# FPGA_PWR_CONFIG.net
KiCad netlist of a schematic drawn in Altium Designer
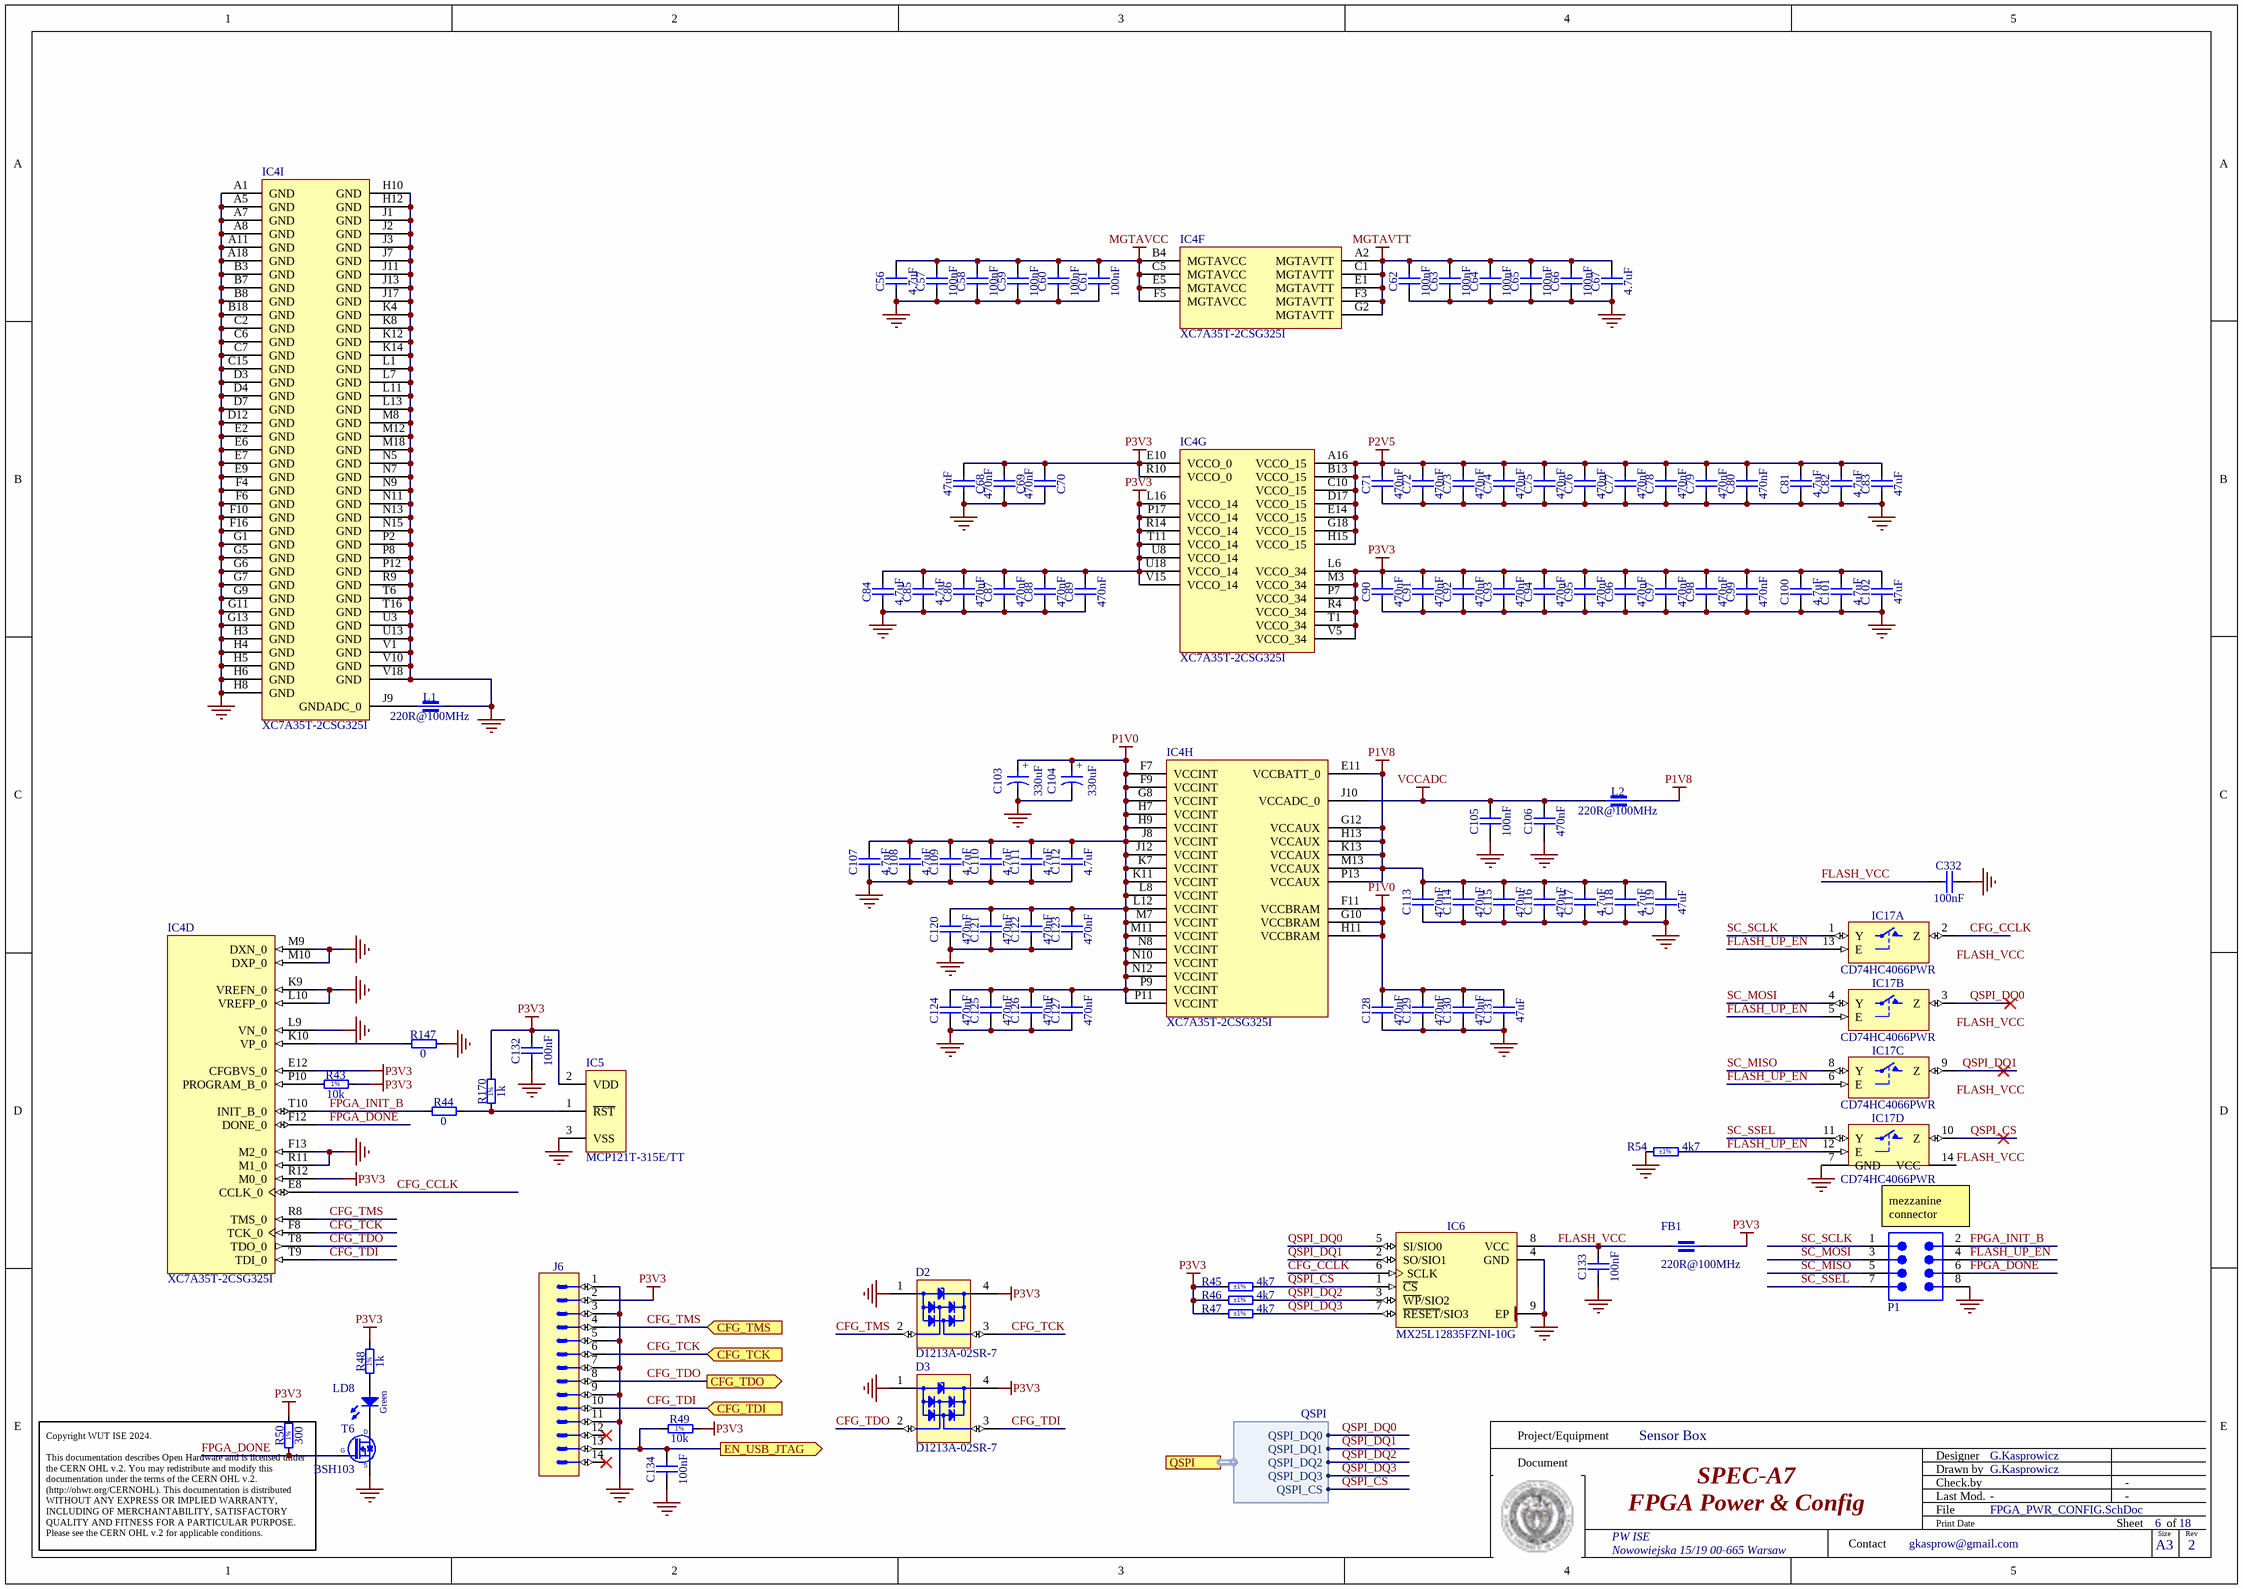
[diagram p0: FPGA_PWR_CONFIG.SchDoc]

(export (version "E")
  (design (tool "Eeschema 10.0.6"))
  (components
    (comp (ref "C56")
      (value "4.7uF")
      (footprint "CAPC1005X55N")
      (description "Non-polarised capacitor")
      (fields
        (field (name "PART NUMBER") "CC0402_4.7UF_6.3V_20%_X5R")
        (field (name "VOLTAGE") "6.3V")
        (field (name "AUTHOR") "CERN DEM JLC")
      )
      (libsource (lib "Capacitors") (part "Capacitor - non polarized"))
    )
    (comp (ref "C57")
      (value "100nF")
      (footprint "CAPC0603X33N")
      (description "Non-polarised capacitor")
      (fields
        (field (name "PART NUMBER") "CC0201_100NF_6.3V_10%_X5R")
        (field (name "VOLTAGE") "6.3V")
        (field (name "AUTHOR") "CERN DEM JLC")
      )
      (libsource (lib "Capacitors") (part "Capacitor - non polarized"))
    )
    (comp (ref "C58")
      (value "100nF")
      (footprint "CAPC0603X33N")
      (description "Non-polarised capacitor")
      (fields
        (field (name "PART NUMBER") "CC0201_100NF_6.3V_10%_X5R")
        (field (name "VOLTAGE") "6.3V")
        (field (name "AUTHOR") "CERN DEM JLC")
      )
      (libsource (lib "Capacitors") (part "Capacitor - non polarized"))
    )
    (comp (ref "C59")
      (value "100nF")
      (footprint "CAPC0603X33N")
      (description "Non-polarised capacitor")
      (fields
        (field (name "PART NUMBER") "CC0201_100NF_6.3V_10%_X5R")
        (field (name "VOLTAGE") "6.3V")
        (field (name "AUTHOR") "CERN DEM JLC")
      )
      (libsource (lib "Capacitors") (part "Capacitor - non polarized"))
    )
    (comp (ref "C60")
      (value "100nF")
      (footprint "CAPC0603X33N")
      (description "Non-polarised capacitor")
      (fields
        (field (name "PART NUMBER") "CC0201_100NF_6.3V_10%_X5R")
        (field (name "VOLTAGE") "6.3V")
        (field (name "AUTHOR") "CERN DEM JLC")
      )
      (libsource (lib "Capacitors") (part "Capacitor - non polarized"))
    )
    (comp (ref "C61")
      (value "100nF")
      (footprint "CAPC0603X33N")
      (description "Non-polarised capacitor")
      (fields
        (field (name "PART NUMBER") "CC0201_100NF_6.3V_10%_X5R")
        (field (name "VOLTAGE") "6.3V")
        (field (name "AUTHOR") "CERN DEM JLC")
      )
      (libsource (lib "Capacitors") (part "Capacitor - non polarized"))
    )
    (comp (ref "C62")
      (value "100nF")
      (footprint "CAPC0603X33N")
      (description "Non-polarised capacitor")
      (fields
        (field (name "PART NUMBER") "CC0201_100NF_6.3V_10%_X5R")
        (field (name "VOLTAGE") "6.3V")
        (field (name "AUTHOR") "CERN DEM JLC")
      )
      (libsource (lib "Capacitors") (part "Capacitor - non polarized"))
    )
    (comp (ref "C63")
      (value "100nF")
      (footprint "CAPC0603X33N")
      (description "Non-polarised capacitor")
      (fields
        (field (name "PART NUMBER") "CC0201_100NF_6.3V_10%_X5R")
        (field (name "VOLTAGE") "6.3V")
        (field (name "AUTHOR") "CERN DEM JLC")
      )
      (libsource (lib "Capacitors") (part "Capacitor - non polarized"))
    )
    (comp (ref "C64")
      (value "100nF")
      (footprint "CAPC0603X33N")
      (description "Non-polarised capacitor")
      (fields
        (field (name "PART NUMBER") "CC0201_100NF_6.3V_10%_X5R")
        (field (name "VOLTAGE") "6.3V")
        (field (name "AUTHOR") "CERN DEM JLC")
      )
      (libsource (lib "Capacitors") (part "Capacitor - non polarized"))
    )
    (comp (ref "C65")
      (value "100nF")
      (footprint "CAPC0603X33N")
      (description "Non-polarised capacitor")
      (fields
        (field (name "PART NUMBER") "CC0201_100NF_6.3V_10%_X5R")
        (field (name "VOLTAGE") "6.3V")
        (field (name "AUTHOR") "CERN DEM JLC")
      )
      (libsource (lib "Capacitors") (part "Capacitor - non polarized"))
    )
    (comp (ref "C66")
      (value "100nF")
      (footprint "CAPC0603X33N")
      (description "Non-polarised capacitor")
      (fields
        (field (name "PART NUMBER") "CC0201_100NF_6.3V_10%_X5R")
        (field (name "VOLTAGE") "6.3V")
        (field (name "AUTHOR") "CERN DEM JLC")
      )
      (libsource (lib "Capacitors") (part "Capacitor - non polarized"))
    )
    (comp (ref "C67")
      (value "4.7uF")
      (footprint "CAPC1005X55N")
      (description "Non-polarised capacitor")
      (fields
        (field (name "PART NUMBER") "CC0402_4.7UF_6.3V_20%_X5R")
        (field (name "VOLTAGE") "6.3V")
        (field (name "AUTHOR") "CERN DEM JLC")
      )
      (libsource (lib "Capacitors") (part "Capacitor - non polarized"))
    )
    (comp (ref "C68")
      (value "47uF")
      (footprint "CAPC1608X100N")
      (description "Non-polarised capacitor")
      (fields
        (field (name "PART NUMBER") "CC0603_47UF_6.3V_20%_X5R")
        (field (name "VOLTAGE") "6.3V")
        (field (name "AUTHOR") "CERN DEM JLC")
      )
      (libsource (lib "Capacitors") (part "Capacitor - non polarized"))
    )
    (comp (ref "C69")
      (value "470nF")
      (footprint "CAPC0603X33N")
      (description "Non-polarised capacitor")
      (fields
        (field (name "PART NUMBER") "CC0201_470NF_4V_20%_X5R")
        (field (name "VOLTAGE") "4V")
        (field (name "AUTHOR") "CERN DEM JLC")
      )
      (libsource (lib "Capacitors") (part "Capacitor - non polarized"))
    )
    (comp (ref "C70")
      (value "470nF")
      (footprint "CAPC0603X33N")
      (description "Non-polarised capacitor")
      (fields
        (field (name "PART NUMBER") "CC0201_470NF_4V_20%_X5R")
        (field (name "VOLTAGE") "4V")
        (field (name "AUTHOR") "CERN DEM JLC")
      )
      (libsource (lib "Capacitors") (part "Capacitor - non polarized"))
    )
    (comp (ref "C71")
      (value "470nF")
      (footprint "CAPC0603X33N")
      (description "Non-polarised capacitor")
      (fields
        (field (name "PART NUMBER") "CC0201_470NF_4V_20%_X5R")
        (field (name "VOLTAGE") "4V")
        (field (name "AUTHOR") "CERN DEM JLC")
      )
      (libsource (lib "Capacitors") (part "Capacitor - non polarized"))
    )
    (comp (ref "C72")
      (value "470nF")
      (footprint "CAPC0603X33N")
      (description "Non-polarised capacitor")
      (fields
        (field (name "PART NUMBER") "CC0201_470NF_4V_20%_X5R")
        (field (name "VOLTAGE") "4V")
        (field (name "AUTHOR") "CERN DEM JLC")
      )
      (libsource (lib "Capacitors") (part "Capacitor - non polarized"))
    )
    (comp (ref "C73")
      (value "470nF")
      (footprint "CAPC0603X33N")
      (description "Non-polarised capacitor")
      (fields
        (field (name "PART NUMBER") "CC0201_470NF_4V_20%_X5R")
        (field (name "VOLTAGE") "4V")
        (field (name "AUTHOR") "CERN DEM JLC")
      )
      (libsource (lib "Capacitors") (part "Capacitor - non polarized"))
    )
    (comp (ref "C74")
      (value "470nF")
      (footprint "CAPC0603X33N")
      (description "Non-polarised capacitor")
      (fields
        (field (name "PART NUMBER") "CC0201_470NF_4V_20%_X5R")
        (field (name "VOLTAGE") "4V")
        (field (name "AUTHOR") "CERN DEM JLC")
      )
      (libsource (lib "Capacitors") (part "Capacitor - non polarized"))
    )
    (comp (ref "C75")
      (value "470nF")
      (footprint "CAPC0603X33N")
      (description "Non-polarised capacitor")
      (fields
        (field (name "PART NUMBER") "CC0201_470NF_4V_20%_X5R")
        (field (name "VOLTAGE") "4V")
        (field (name "AUTHOR") "CERN DEM JLC")
      )
      (libsource (lib "Capacitors") (part "Capacitor - non polarized"))
    )
    (comp (ref "C76")
      (value "470nF")
      (footprint "CAPC0603X33N")
      (description "Non-polarised capacitor")
      (fields
        (field (name "PART NUMBER") "CC0201_470NF_4V_20%_X5R")
        (field (name "VOLTAGE") "4V")
        (field (name "AUTHOR") "CERN DEM JLC")
      )
      (libsource (lib "Capacitors") (part "Capacitor - non polarized"))
    )
    (comp (ref "C77")
      (value "470nF")
      (footprint "CAPC0603X33N")
      (description "Non-polarised capacitor")
      (fields
        (field (name "PART NUMBER") "CC0201_470NF_4V_20%_X5R")
        (field (name "VOLTAGE") "4V")
        (field (name "AUTHOR") "CERN DEM JLC")
      )
      (libsource (lib "Capacitors") (part "Capacitor - non polarized"))
    )
    (comp (ref "C78")
      (value "470nF")
      (footprint "CAPC0603X33N")
      (description "Non-polarised capacitor")
      (fields
        (field (name "PART NUMBER") "CC0201_470NF_4V_20%_X5R")
        (field (name "VOLTAGE") "4V")
        (field (name "AUTHOR") "CERN DEM JLC")
      )
      (libsource (lib "Capacitors") (part "Capacitor - non polarized"))
    )
    (comp (ref "C79")
      (value "470nF")
      (footprint "CAPC0603X33N")
      (description "Non-polarised capacitor")
      (fields
        (field (name "PART NUMBER") "CC0201_470NF_4V_20%_X5R")
        (field (name "VOLTAGE") "4V")
        (field (name "AUTHOR") "CERN DEM JLC")
      )
      (libsource (lib "Capacitors") (part "Capacitor - non polarized"))
    )
    (comp (ref "C80")
      (value "470nF")
      (footprint "CAPC0603X33N")
      (description "Non-polarised capacitor")
      (fields
        (field (name "PART NUMBER") "CC0201_470NF_4V_20%_X5R")
        (field (name "VOLTAGE") "4V")
        (field (name "AUTHOR") "CERN DEM JLC")
      )
      (libsource (lib "Capacitors") (part "Capacitor - non polarized"))
    )
    (comp (ref "C81")
      (value "4.7uF")
      (footprint "CAPC1005X55N")
      (description "Non-polarised capacitor")
      (fields
        (field (name "PART NUMBER") "CC0402_4.7UF_6.3V_20%_X5R")
        (field (name "VOLTAGE") "6.3V")
        (field (name "AUTHOR") "CERN DEM JLC")
      )
      (libsource (lib "Capacitors") (part "Capacitor - non polarized"))
    )
    (comp (ref "C82")
      (value "4.7uF")
      (footprint "CAPC1005X55N")
      (description "Non-polarised capacitor")
      (fields
        (field (name "PART NUMBER") "CC0402_4.7UF_6.3V_20%_X5R")
        (field (name "VOLTAGE") "6.3V")
        (field (name "AUTHOR") "CERN DEM JLC")
      )
      (libsource (lib "Capacitors") (part "Capacitor - non polarized"))
    )
    (comp (ref "C83")
      (value "47uF")
      (footprint "CAPC1608X100N")
      (description "Non-polarised capacitor")
      (fields
        (field (name "PART NUMBER") "CC0603_47UF_6.3V_20%_X5R")
        (field (name "VOLTAGE") "6.3V")
        (field (name "AUTHOR") "CERN DEM JLC")
      )
      (libsource (lib "Capacitors") (part "Capacitor - non polarized"))
    )
    (comp (ref "C84")
      (value "4.7uF")
      (footprint "CAPC1005X55N")
      (description "Non-polarised capacitor")
      (fields
        (field (name "PART NUMBER") "CC0402_4.7UF_6.3V_20%_X5R")
        (field (name "VOLTAGE") "6.3V")
        (field (name "AUTHOR") "CERN DEM JLC")
      )
      (libsource (lib "Capacitors") (part "Capacitor - non polarized"))
    )
    (comp (ref "C85")
      (value "4.7uF")
      (footprint "CAPC1005X55N")
      (description "Non-polarised capacitor")
      (fields
        (field (name "PART NUMBER") "CC0402_4.7UF_6.3V_20%_X5R")
        (field (name "VOLTAGE") "6.3V")
        (field (name "AUTHOR") "CERN DEM JLC")
      )
      (libsource (lib "Capacitors") (part "Capacitor - non polarized"))
    )
    (comp (ref "C86")
      (value "470nF")
      (footprint "CAPC0603X33N")
      (description "Non-polarised capacitor")
      (fields
        (field (name "PART NUMBER") "CC0201_470NF_4V_20%_X5R")
        (field (name "VOLTAGE") "4V")
        (field (name "AUTHOR") "CERN DEM JLC")
      )
      (libsource (lib "Capacitors") (part "Capacitor - non polarized"))
    )
    (comp (ref "C87")
      (value "470nF")
      (footprint "CAPC0603X33N")
      (description "Non-polarised capacitor")
      (fields
        (field (name "PART NUMBER") "CC0201_470NF_4V_20%_X5R")
        (field (name "VOLTAGE") "4V")
        (field (name "AUTHOR") "CERN DEM JLC")
      )
      (libsource (lib "Capacitors") (part "Capacitor - non polarized"))
    )
    (comp (ref "C88")
      (value "470nF")
      (footprint "CAPC0603X33N")
      (description "Non-polarised capacitor")
      (fields
        (field (name "PART NUMBER") "CC0201_470NF_4V_20%_X5R")
        (field (name "VOLTAGE") "4V")
        (field (name "AUTHOR") "CERN DEM JLC")
      )
      (libsource (lib "Capacitors") (part "Capacitor - non polarized"))
    )
    (comp (ref "C89")
      (value "470nF")
      (footprint "CAPC0603X33N")
      (description "Non-polarised capacitor")
      (fields
        (field (name "PART NUMBER") "CC0201_470NF_4V_20%_X5R")
        (field (name "VOLTAGE") "4V")
        (field (name "AUTHOR") "CERN DEM JLC")
      )
      (libsource (lib "Capacitors") (part "Capacitor - non polarized"))
    )
    (comp (ref "C90")
      (value "470nF")
      (footprint "CAPC0603X33N")
      (description "Non-polarised capacitor")
      (fields
        (field (name "PART NUMBER") "CC0201_470NF_4V_20%_X5R")
        (field (name "VOLTAGE") "4V")
        (field (name "AUTHOR") "CERN DEM JLC")
      )
      (libsource (lib "Capacitors") (part "Capacitor - non polarized"))
    )
    (comp (ref "C91")
      (value "470nF")
      (footprint "CAPC0603X33N")
      (description "Non-polarised capacitor")
      (fields
        (field (name "PART NUMBER") "CC0201_470NF_4V_20%_X5R")
        (field (name "VOLTAGE") "4V")
        (field (name "AUTHOR") "CERN DEM JLC")
      )
      (libsource (lib "Capacitors") (part "Capacitor - non polarized"))
    )
    (comp (ref "C92")
      (value "470nF")
      (footprint "CAPC0603X33N")
      (description "Non-polarised capacitor")
      (fields
        (field (name "PART NUMBER") "CC0201_470NF_4V_20%_X5R")
        (field (name "VOLTAGE") "4V")
        (field (name "AUTHOR") "CERN DEM JLC")
      )
      (libsource (lib "Capacitors") (part "Capacitor - non polarized"))
    )
    (comp (ref "C93")
      (value "470nF")
      (footprint "CAPC0603X33N")
      (description "Non-polarised capacitor")
      (fields
        (field (name "PART NUMBER") "CC0201_470NF_4V_20%_X5R")
        (field (name "VOLTAGE") "4V")
        (field (name "AUTHOR") "CERN DEM JLC")
      )
      (libsource (lib "Capacitors") (part "Capacitor - non polarized"))
    )
    (comp (ref "C94")
      (value "470nF")
      (footprint "CAPC0603X33N")
      (description "Non-polarised capacitor")
      (fields
        (field (name "PART NUMBER") "CC0201_470NF_4V_20%_X5R")
        (field (name "VOLTAGE") "4V")
        (field (name "AUTHOR") "CERN DEM JLC")
      )
      (libsource (lib "Capacitors") (part "Capacitor - non polarized"))
    )
    (comp (ref "C95")
      (value "470nF")
      (footprint "CAPC0603X33N")
      (description "Non-polarised capacitor")
      (fields
        (field (name "PART NUMBER") "CC0201_470NF_4V_20%_X5R")
        (field (name "VOLTAGE") "4V")
        (field (name "AUTHOR") "CERN DEM JLC")
      )
      (libsource (lib "Capacitors") (part "Capacitor - non polarized"))
    )
    (comp (ref "C96")
      (value "470nF")
      (footprint "CAPC0603X33N")
      (description "Non-polarised capacitor")
      (fields
        (field (name "PART NUMBER") "CC0201_470NF_4V_20%_X5R")
        (field (name "VOLTAGE") "4V")
        (field (name "AUTHOR") "CERN DEM JLC")
      )
      (libsource (lib "Capacitors") (part "Capacitor - non polarized"))
    )
    (comp (ref "C97")
      (value "470nF")
      (footprint "CAPC0603X33N")
      (description "Non-polarised capacitor")
      (fields
        (field (name "PART NUMBER") "CC0201_470NF_4V_20%_X5R")
        (field (name "VOLTAGE") "4V")
        (field (name "AUTHOR") "CERN DEM JLC")
      )
      (libsource (lib "Capacitors") (part "Capacitor - non polarized"))
    )
    (comp (ref "C98")
      (value "470nF")
      (footprint "CAPC0603X33N")
      (description "Non-polarised capacitor")
      (fields
        (field (name "PART NUMBER") "CC0201_470NF_4V_20%_X5R")
        (field (name "VOLTAGE") "4V")
        (field (name "AUTHOR") "CERN DEM JLC")
      )
      (libsource (lib "Capacitors") (part "Capacitor - non polarized"))
    )
    (comp (ref "C99")
      (value "470nF")
      (footprint "CAPC0603X33N")
      (description "Non-polarised capacitor")
      (fields
        (field (name "PART NUMBER") "CC0201_470NF_4V_20%_X5R")
        (field (name "VOLTAGE") "4V")
        (field (name "AUTHOR") "CERN DEM JLC")
      )
      (libsource (lib "Capacitors") (part "Capacitor - non polarized"))
    )
    (comp (ref "C100")
      (value "4.7uF")
      (footprint "CAPC1005X55N")
      (description "Non-polarised capacitor")
      (fields
        (field (name "PART NUMBER") "CC0402_4.7UF_6.3V_20%_X5R")
        (field (name "VOLTAGE") "6.3V")
        (field (name "AUTHOR") "CERN DEM JLC")
      )
      (libsource (lib "Capacitors") (part "Capacitor - non polarized"))
    )
    (comp (ref "C101")
      (value "4.7uF")
      (footprint "CAPC1005X55N")
      (description "Non-polarised capacitor")
      (fields
        (field (name "PART NUMBER") "CC0402_4.7UF_6.3V_20%_X5R")
        (field (name "VOLTAGE") "6.3V")
        (field (name "AUTHOR") "CERN DEM JLC")
      )
      (libsource (lib "Capacitors") (part "Capacitor - non polarized"))
    )
    (comp (ref "C102")
      (value "47uF")
      (footprint "CAPC1608X100N")
      (description "Non-polarised capacitor")
      (fields
        (field (name "PART NUMBER") "CC0603_47UF_6.3V_20%_X5R")
        (field (name "VOLTAGE") "6.3V")
        (field (name "AUTHOR") "CERN DEM JLC")
      )
      (libsource (lib "Capacitors") (part "Capacitor - non polarized"))
    )
    (comp (ref "C103")
      (value "330uF")
      (footprint "CAPMP7343X190N")
      (description "Polarised capacitor")
      (fields
        (field (name "PART NUMBER") "CTE7343-19_330UF_2.5V_20%_LESR0025_KEMET_T520")
        (field (name "VOLTAGE") "2.5V")
        (field (name "AUTHOR") "CERN DEM MR")
      )
      (libsource (lib "Capacitors") (part "Capacitor - polarized"))
    )
    (comp (ref "C104")
      (value "330uF")
      (footprint "CAPMP7343X190N")
      (description "Polarised capacitor")
      (fields
        (field (name "PART NUMBER") "CTE7343-19_330UF_2.5V_20%_LESR0025_KEMET_T520")
        (field (name "VOLTAGE") "2.5V")
        (field (name "AUTHOR") "CERN DEM MR")
      )
      (libsource (lib "Capacitors") (part "Capacitor - polarized"))
    )
    (comp (ref "C105")
      (value "100nF")
      (footprint "CAPC0603X33N")
      (description "Non-polarised capacitor")
      (fields
        (field (name "PART NUMBER") "CC0201_100NF_6.3V_10%_X5R")
        (field (name "VOLTAGE") "6.3V")
        (field (name "AUTHOR") "CERN DEM JLC")
      )
      (libsource (lib "Capacitors") (part "Capacitor - non polarized"))
    )
    (comp (ref "C106")
      (value "470nF")
      (footprint "CAPC0603X33N")
      (description "Non-polarised capacitor")
      (fields
        (field (name "PART NUMBER") "CC0201_470NF_4V_20%_X5R")
        (field (name "VOLTAGE") "4V")
        (field (name "AUTHOR") "CERN DEM JLC")
      )
      (libsource (lib "Capacitors") (part "Capacitor - non polarized"))
    )
    (comp (ref "C107")
      (value "4.7uF")
      (footprint "CAPC1005X55N")
      (description "Non-polarised capacitor")
      (fields
        (field (name "PART NUMBER") "CC0402_4.7UF_6.3V_20%_X5R")
        (field (name "VOLTAGE") "6.3V")
        (field (name "AUTHOR") "CERN DEM JLC")
      )
      (libsource (lib "Capacitors") (part "Capacitor - non polarized"))
    )
    (comp (ref "C108")
      (value "4.7uF")
      (footprint "CAPC1005X55N")
      (description "Non-polarised capacitor")
      (fields
        (field (name "PART NUMBER") "CC0402_4.7UF_6.3V_20%_X5R")
        (field (name "VOLTAGE") "6.3V")
        (field (name "AUTHOR") "CERN DEM JLC")
      )
      (libsource (lib "Capacitors") (part "Capacitor - non polarized"))
    )
    (comp (ref "C109")
      (value "4.7uF")
      (footprint "CAPC1005X55N")
      (description "Non-polarised capacitor")
      (fields
        (field (name "PART NUMBER") "CC0402_4.7UF_6.3V_20%_X5R")
        (field (name "VOLTAGE") "6.3V")
        (field (name "AUTHOR") "CERN DEM JLC")
      )
      (libsource (lib "Capacitors") (part "Capacitor - non polarized"))
    )
    (comp (ref "C110")
      (value "4.7uF")
      (footprint "CAPC1005X55N")
      (description "Non-polarised capacitor")
      (fields
        (field (name "PART NUMBER") "CC0402_4.7UF_6.3V_20%_X5R")
        (field (name "VOLTAGE") "6.3V")
        (field (name "AUTHOR") "CERN DEM JLC")
      )
      (libsource (lib "Capacitors") (part "Capacitor - non polarized"))
    )
    (comp (ref "C111")
      (value "4.7uF")
      (footprint "CAPC1005X55N")
      (description "Non-polarised capacitor")
      (fields
        (field (name "PART NUMBER") "CC0402_4.7UF_6.3V_20%_X5R")
        (field (name "VOLTAGE") "6.3V")
        (field (name "AUTHOR") "CERN DEM JLC")
      )
      (libsource (lib "Capacitors") (part "Capacitor - non polarized"))
    )
    (comp (ref "C112")
      (value "4.7uF")
      (footprint "CAPC1005X55N")
      (description "Non-polarised capacitor")
      (fields
        (field (name "PART NUMBER") "CC0402_4.7UF_6.3V_20%_X5R")
        (field (name "VOLTAGE") "6.3V")
        (field (name "AUTHOR") "CERN DEM JLC")
      )
      (libsource (lib "Capacitors") (part "Capacitor - non polarized"))
    )
    (comp (ref "C113")
      (value "470nF")
      (footprint "CAPC0603X33N")
      (description "Non-polarised capacitor")
      (fields
        (field (name "PART NUMBER") "CC0201_470NF_4V_20%_X5R")
        (field (name "VOLTAGE") "4V")
        (field (name "AUTHOR") "CERN DEM JLC")
      )
      (libsource (lib "Capacitors") (part "Capacitor - non polarized"))
    )
    (comp (ref "C114")
      (value "470nF")
      (footprint "CAPC0603X33N")
      (description "Non-polarised capacitor")
      (fields
        (field (name "PART NUMBER") "CC0201_470NF_4V_20%_X5R")
        (field (name "VOLTAGE") "4V")
        (field (name "AUTHOR") "CERN DEM JLC")
      )
      (libsource (lib "Capacitors") (part "Capacitor - non polarized"))
    )
    (comp (ref "C115")
      (value "470nF")
      (footprint "CAPC0603X33N")
      (description "Non-polarised capacitor")
      (fields
        (field (name "PART NUMBER") "CC0201_470NF_4V_20%_X5R")
        (field (name "VOLTAGE") "4V")
        (field (name "AUTHOR") "CERN DEM JLC")
      )
      (libsource (lib "Capacitors") (part "Capacitor - non polarized"))
    )
    (comp (ref "C116")
      (value "470nF")
      (footprint "CAPC0603X33N")
      (description "Non-polarised capacitor")
      (fields
        (field (name "PART NUMBER") "CC0201_470NF_4V_20%_X5R")
        (field (name "VOLTAGE") "4V")
        (field (name "AUTHOR") "CERN DEM JLC")
      )
      (libsource (lib "Capacitors") (part "Capacitor - non polarized"))
    )
    (comp (ref "C117")
      (value "4.7uF")
      (footprint "CAPC1005X55N")
      (description "Non-polarised capacitor")
      (fields
        (field (name "PART NUMBER") "CC0402_4.7UF_6.3V_20%_X5R")
        (field (name "VOLTAGE") "6.3V")
        (field (name "AUTHOR") "CERN DEM JLC")
      )
      (libsource (lib "Capacitors") (part "Capacitor - non polarized"))
    )
    (comp (ref "C118")
      (value "4.7uF")
      (footprint "CAPC1005X55N")
      (description "Non-polarised capacitor")
      (fields
        (field (name "PART NUMBER") "CC0402_4.7UF_6.3V_20%_X5R")
        (field (name "VOLTAGE") "6.3V")
        (field (name "AUTHOR") "CERN DEM JLC")
      )
      (libsource (lib "Capacitors") (part "Capacitor - non polarized"))
    )
    (comp (ref "C119")
      (value "47uF")
      (footprint "CAPC1608X100N")
      (description "Non-polarised capacitor")
      (fields
        (field (name "PART NUMBER") "CC0603_47UF_6.3V_20%_X5R")
        (field (name "VOLTAGE") "6.3V")
        (field (name "AUTHOR") "CERN DEM JLC")
      )
      (libsource (lib "Capacitors") (part "Capacitor - non polarized"))
    )
    (comp (ref "C120")
      (value "470nF")
      (footprint "CAPC0603X33N")
      (description "Non-polarised capacitor")
      (fields
        (field (name "PART NUMBER") "CC0201_470NF_4V_20%_X5R")
        (field (name "VOLTAGE") "4V")
        (field (name "AUTHOR") "CERN DEM JLC")
      )
      (libsource (lib "Capacitors") (part "Capacitor - non polarized"))
    )
    (comp (ref "C121")
      (value "470nF")
      (footprint "CAPC0603X33N")
      (description "Non-polarised capacitor")
      (fields
        (field (name "PART NUMBER") "CC0201_470NF_4V_20%_X5R")
        (field (name "VOLTAGE") "4V")
        (field (name "AUTHOR") "CERN DEM JLC")
      )
      (libsource (lib "Capacitors") (part "Capacitor - non polarized"))
    )
    (comp (ref "C122")
      (value "470nF")
      (footprint "CAPC0603X33N")
      (description "Non-polarised capacitor")
      (fields
        (field (name "PART NUMBER") "CC0201_470NF_4V_20%_X5R")
        (field (name "VOLTAGE") "4V")
        (field (name "AUTHOR") "CERN DEM JLC")
      )
      (libsource (lib "Capacitors") (part "Capacitor - non polarized"))
    )
    (comp (ref "C123")
      (value "470nF")
      (footprint "CAPC0603X33N")
      (description "Non-polarised capacitor")
      (fields
        (field (name "PART NUMBER") "CC0201_470NF_4V_20%_X5R")
        (field (name "VOLTAGE") "4V")
        (field (name "AUTHOR") "CERN DEM JLC")
      )
      (libsource (lib "Capacitors") (part "Capacitor - non polarized"))
    )
    (comp (ref "C124")
      (value "470nF")
      (footprint "CAPC0603X33N")
      (description "Non-polarised capacitor")
      (fields
        (field (name "PART NUMBER") "CC0201_470NF_4V_20%_X5R")
        (field (name "VOLTAGE") "4V")
        (field (name "AUTHOR") "CERN DEM JLC")
      )
      (libsource (lib "Capacitors") (part "Capacitor - non polarized"))
    )
    (comp (ref "C125")
      (value "470nF")
      (footprint "CAPC0603X33N")
      (description "Non-polarised capacitor")
      (fields
        (field (name "PART NUMBER") "CC0201_470NF_4V_20%_X5R")
        (field (name "VOLTAGE") "4V")
        (field (name "AUTHOR") "CERN DEM JLC")
      )
      (libsource (lib "Capacitors") (part "Capacitor - non polarized"))
    )
    (comp (ref "C126")
      (value "470nF")
      (footprint "CAPC0603X33N")
      (description "Non-polarised capacitor")
      (fields
        (field (name "PART NUMBER") "CC0201_470NF_4V_20%_X5R")
        (field (name "VOLTAGE") "4V")
        (field (name "AUTHOR") "CERN DEM JLC")
      )
      (libsource (lib "Capacitors") (part "Capacitor - non polarized"))
    )
    (comp (ref "C127")
      (value "470nF")
      (footprint "CAPC0603X33N")
      (description "Non-polarised capacitor")
      (fields
        (field (name "PART NUMBER") "CC0201_470NF_4V_20%_X5R")
        (field (name "VOLTAGE") "4V")
        (field (name "AUTHOR") "CERN DEM JLC")
      )
      (libsource (lib "Capacitors") (part "Capacitor - non polarized"))
    )
    (comp (ref "C128")
      (value "470nF")
      (footprint "CAPC0603X33N")
      (description "Non-polarised capacitor")
      (fields
        (field (name "PART NUMBER") "CC0201_470NF_4V_20%_X5R")
        (field (name "VOLTAGE") "4V")
        (field (name "AUTHOR") "CERN DEM JLC")
      )
      (libsource (lib "Capacitors") (part "Capacitor - non polarized"))
    )
    (comp (ref "C129")
      (value "470nF")
      (footprint "CAPC0603X33N")
      (description "Non-polarised capacitor")
      (fields
        (field (name "PART NUMBER") "CC0201_470NF_4V_20%_X5R")
        (field (name "VOLTAGE") "4V")
        (field (name "AUTHOR") "CERN DEM JLC")
      )
      (libsource (lib "Capacitors") (part "Capacitor - non polarized"))
    )
    (comp (ref "C130")
      (value "470nF")
      (footprint "CAPC0603X33N")
      (description "Non-polarised capacitor")
      (fields
        (field (name "PART NUMBER") "CC0201_470NF_4V_20%_X5R")
        (field (name "VOLTAGE") "4V")
        (field (name "AUTHOR") "CERN DEM JLC")
      )
      (libsource (lib "Capacitors") (part "Capacitor - non polarized"))
    )
    (comp (ref "C131")
      (value "47uF")
      (footprint "CAPC1608X100N")
      (description "Non-polarised capacitor")
      (fields
        (field (name "PART NUMBER") "CC0603_47UF_6.3V_20%_X5R")
        (field (name "VOLTAGE") "6.3V")
        (field (name "AUTHOR") "CERN DEM JLC")
      )
      (libsource (lib "Capacitors") (part "Capacitor - non polarized"))
    )
    (comp (ref "C132")
      (value "100nF")
      (footprint "CAPC0603X33N")
      (description "Non-polarised capacitor")
      (fields
        (field (name "PART NUMBER") "CC0201_100NF_6.3V_10%_X5R")
        (field (name "VOLTAGE") "6.3V")
        (field (name "AUTHOR") "CERN DEM JLC")
      )
      (libsource (lib "Capacitors") (part "Capacitor - non polarized"))
    )
    (comp (ref "C133")
      (value "100nF")
      (footprint "CAPC0603X33N")
      (description "Non-polarised capacitor")
      (fields
        (field (name "PART NUMBER") "CC0201_100NF_6.3V_10%_X5R")
        (field (name "VOLTAGE") "6.3V")
        (field (name "AUTHOR") "CERN DEM JLC")
      )
      (libsource (lib "Capacitors") (part "Capacitor - non polarized"))
    )
    (comp (ref "C134")
      (value "100nF")
      (footprint "CAPC0603X33N")
      (description "Non-polarised capacitor")
      (fields
        (field (name "PART NUMBER") "CC0201_100NF_6.3V_10%_X5R")
        (field (name "VOLTAGE") "6.3V")
        (field (name "AUTHOR") "CERN DEM JLC")
      )
      (libsource (lib "Capacitors") (part "Capacitor - non polarized"))
    )
    (comp (ref "C332")
      (value "100nF")
      (footprint "CAPC0603X33N")
      (description "Non-polarised capacitor")
      (fields
        (field (name "PART NUMBER") "CC0201_100NF_6.3V_10%_X5R")
        (field (name "VOLTAGE") "6.3V")
        (field (name "AUTHOR") "CERN DEM JLC")
      )
      (libsource (lib "Capacitors") (part "Capacitor - non polarized"))
    )
    (comp (ref "D2")
      (value "D1213A-02SR-7")
      (footprint "SOT190P238X100-4N")
      (description "D1213A-02SR Series 400 mW Uni-Directional Surface Mount TVS Diode - SOT-143")
      (libsource (lib "TechnoSystem Workspace") (part "D1213A-02SR-7"))
    )
    (comp (ref "D3")
      (value "D1213A-02SR-7")
      (footprint "SOT190P238X100-4N")
      (description "D1213A-02SR Series 400 mW Uni-Directional Surface Mount TVS Diode - SOT-143")
      (libsource (lib "TechnoSystem Workspace") (part "D1213A-02SR-7"))
    )
    (comp (ref "FB1")
      (value "220R@100MHz")
      (footprint "INDC1608X95N")
      (fields
        (field (name "TOLERANCE") "±25%")
        (field (name "PART NUMBER") "IND0603_MURATA_BLM18SG221TN1")
        (field (name "POWER") "2.5A")
        (field (name "AUTHOR") "CERN DEM MR")
      )
      (libsource (lib "Inductors & Transformers") (part "Ferrite Bead"))
    )
    (comp (ref "IC4")
      (value "XC7A35T-2CSG325I")
      (footprint "CSG325")
      (description "Artix-7 FPGA, 150 User I/Os, 4 GTP, 324-Ball BGA, Speed Grade 2, Industrial Grade, Pb-Free")
      (fields (field (name "MANUFACTURER") "Xilinx"))
      (libsource (lib "") (part "XLNX-XC7A35T-CSG325_1"))
    )
    (comp (ref "IC5")
      (value "MCP121T-315E/TT")
      (footprint "SOT-23-TT3_L")
      (description "Micropower Voltage Supervisors, 3-Pin SOT-23, Extended Temperature, Tape and Reel")
      (libsource (lib "Altium Content Vault") (part "PM-SCCT-MCP121-3"))
    )
    (comp (ref "IC6")
      (value "MX25L12835FZNI-10G")
      (footprint "SON127P600X500X80-9N-R350X410")
      (description "128Mb, 3V, Serial Multi I/O Flash Memory")
      (fields (field (name "MANUFACTURER") "MACRONIX") (field (name "AUTHOR") "CERN DEM HF"))
      (libsource (lib "ICs And Semiconductors") (part "MX25L12835FZNI-10G"))
    )
    (comp (ref "IC17")
      (value "CD74HC4066PWR")
      (footprint "CD74HC4066PWR")
      (description "12-V, 1: 1 (SPST), (SPST), 4-channel analog switch 14-TSSOP -55 to 125")
      (libsource (lib "TechnoSystem Workspace") (part "CD74HC4066PWR-Symbol-1"))
    )
    (comp (ref "J6")
      (value "Milli-Grid™")
      (footprint "MOLEX_87832-1420")
      (description "Connector 14 Male")
      (fields
        (field (name "PART NUMBER") "MOLEX_87832-1420")
        (field (name "MANUFACTURER") "MOLEX")
        (field (name "AUTHOR") "CERN DEM JLC")
      )
      (libsource (lib "Connectors") (part "Connector 14 Male"))
    )
    (comp (ref "L1")
      (value "220R@100MHz")
      (footprint "INDC1005X55N")
      (fields
        (field (name "PART NUMBER") "IND0402_MURATA_BLM15HB221SN1")
        (field (name "POWER") "250mA")
        (field (name "TOLERANCE") "±25%")
        (field (name "AUTHOR") "CERN DEM JLC")
      )
      (libsource (lib "") (part "Ferrite Bead_1"))
    )
    (comp (ref "L2")
      (value "220R@100MHz")
      (footprint "INDC1005X55N")
      (fields
        (field (name "PART NUMBER") "IND0402_MURATA_BLM15HB221SN1")
        (field (name "POWER") "250mA")
        (field (name "TOLERANCE") "±25%")
        (field (name "AUTHOR") "CERN DEM JLC")
      )
      (libsource (lib "") (part "Ferrite Bead_1"))
    )
    (comp (ref "LD8")
      (value "Green")
      (footprint "LED_KINGBRIGHT_KPH-1608CGCK")
      (description "LED Green 1C 2A")
      (fields
        (field (name "MANUFACTURER PART NUMBER") "KPH-1608CGCK")
        (field (name "PART NUMBER") "LED_KINGBRIGHT_KPH-1608CGCK")
        (field (name "AUTHOR") "CERN DEM JLC")
      )
      (libsource (lib "ICs And Semiconductors") (part "LED Green 1C 2A"))
    )
    (comp (ref "P1")
      (value "61300821121")
      (footprint "61300821121")
      (description "WR-PHD Pin Header, THT, Vertical, pitch 2.54mm, 2 Row, 8P")
      (fields (field (name "MANUFACTURER") "Wurth Elektronik"))
      (libsource (lib "Altium_WR-PHD (rev24a)") (part "61300821121"))
    )
    (comp (ref "R43")
      (value "10k")
      (footprint "RESC1005X40N")
      (description "Resistor - 1%")
      (fields
        (field (name "PART NUMBER") "R0402_10K_1%_0.0625W_100PPM")
        (field (name "POWER") "0.0625W")
        (field (name "AUTHOR") "CERN DEM JLC")
      )
      (libsource (lib "Resistors") (part "Resistor - 1%"))
    )
    (comp (ref "R44")
      (value "0")
      (footprint "RESC1005X40N")
      (description "Resistor")
      (fields
        (field (name "PART NUMBER") "R0402_0R_JUMPER")
        (field (name "MANUFACTURER") "GENERIC")
        (field (name "AUTHOR") "CERN DEM JLC")
      )
      (libsource (lib "Resistors") (part "Resistor"))
    )
    (comp (ref "R45")
      (value "4k7")
      (footprint "RESC1005X40N")
      (description "Resistor - 1%")
      (fields
        (field (name "TOLERANCE") "±1%")
        (field (name "PART NUMBER") "R0402_4K7_1%_0.0625W_100PPM")
        (field (name "POWER") "0.0625W")
        (field (name "AUTHOR") "CERN DEM JLC")
      )
      (libsource (lib "Resistors") (part "Resistor - 1%"))
    )
    (comp (ref "R46")
      (value "4k7")
      (footprint "RESC1005X40N")
      (description "Resistor - 1%")
      (fields
        (field (name "TOLERANCE") "±1%")
        (field (name "PART NUMBER") "R0402_4K7_1%_0.0625W_100PPM")
        (field (name "POWER") "0.0625W")
        (field (name "AUTHOR") "CERN DEM JLC")
      )
      (libsource (lib "Resistors") (part "Resistor - 1%"))
    )
    (comp (ref "R47")
      (value "4k7")
      (footprint "RESC1005X40N")
      (description "Resistor - 1%")
      (fields
        (field (name "TOLERANCE") "±1%")
        (field (name "PART NUMBER") "R0402_4K7_1%_0.0625W_100PPM")
        (field (name "POWER") "0.0625W")
        (field (name "AUTHOR") "CERN DEM JLC")
      )
      (libsource (lib "Resistors") (part "Resistor - 1%"))
    )
    (comp (ref "R48")
      (value "1k")
      (footprint "RESC1005X40N")
      (description "Resistor - 1%")
      (fields
        (field (name "PART NUMBER") "R0402_1K_1%_0.0625W_100PPM")
        (field (name "POWER") "0.0625W")
        (field (name "AUTHOR") "CERN DEM JLC")
      )
      (libsource (lib "Resistors") (part "Resistor - 1%"))
    )
    (comp (ref "R49")
      (value "10k")
      (footprint "RESC1005X40N")
      (description "Resistor - 1%")
      (fields
        (field (name "PART NUMBER") "R0402_10K_1%_0.0625W_100PPM")
        (field (name "POWER") "0.0625W")
        (field (name "AUTHOR") "CERN DEM JLC")
      )
      (libsource (lib "Resistors") (part "Resistor - 1%"))
    )
    (comp (ref "R50")
      (value "300")
      (footprint "RESC1005X40N")
      (description "Resistor - 1%")
      (fields
        (field (name "PART NUMBER") "R0402_300R_1%_0.0625W_100PPM")
        (field (name "POWER") "0.0625W")
        (field (name "AUTHOR") "CERN DEM JLC")
      )
      (libsource (lib "Resistors") (part "Resistor - 1%"))
    )
    (comp (ref "R54")
      (value "4k7")
      (footprint "RESC1005X40N")
      (description "Resistor - 1%")
      (fields
        (field (name "TOLERANCE") "±1%")
        (field (name "PART NUMBER") "R0402_4K7_1%_0.0625W_100PPM")
        (field (name "POWER") "0.0625W")
        (field (name "AUTHOR") "CERN DEM JLC")
      )
      (libsource (lib "Resistors") (part "Resistor - 1%"))
    )
    (comp (ref "R147")
      (value "0")
      (footprint "RESC1005X40N")
      (description "Resistor")
      (fields
        (field (name "PART NUMBER") "R0402_0R_JUMPER")
        (field (name "MANUFACTURER") "GENERIC")
        (field (name "AUTHOR") "CERN DEM JLC")
      )
      (libsource (lib "Resistors") (part "Resistor"))
    )
    (comp (ref "R170")
      (value "1k")
      (footprint "RESC1005X40N")
      (description "Resistor - 1%")
      (fields
        (field (name "PART NUMBER") "R0402_1K_1%_0.0625W_100PPM")
        (field (name "POWER") "0.0625W")
        (field (name "AUTHOR") "CERN DEM JLC")
      )
      (libsource (lib "Resistors") (part "Resistor - 1%"))
    )
    (comp (ref "T6")
      (value "BSH103")
      (footprint "SOT95P230X110-3N")
      (description "N-CHANNEL MOSFET WITH DIODE")
      (fields (field (name "MANUFACTURER") "NEXPERIA") (field (name "AUTHOR") "CERN DEM JLC"))
      (libsource (lib "ICs And Semiconductors") (part "N-MOSFET-D 1G 2S 3D"))
    )
  )
  (nets
    (net (code "2") (name "/CFG_CCLK") (class "Default")
      (node (ref "IC17") (pin "2") (pinfunction "Z_2") (pintype "bidirectional"))
      (node (ref "IC4") (pin "E8") (pinfunction "CCLK_0_E8") (pintype "bidirectional"))
      (node (ref "IC6") (pin "6") (pinfunction "SCLK_6") (pintype "input"))
    )
    (net (code "3") (name "/CFG_TCK") (class "Default")
      (node (ref "D2") (pin "3") (pinfunction "I/O2_3") (pintype "bidirectional"))
      (node (ref "IC4") (pin "F8") (pinfunction "TCK_0_F8") (pintype "input"))
      (node (ref "J6") (pin "6") (pinfunction "6_6") (pintype "bidirectional"))
    )
    (net (code "4") (name "/CFG_TDI") (class "Default")
      (node (ref "D3") (pin "3") (pinfunction "I/O2_3") (pintype "bidirectional"))
      (node (ref "IC4") (pin "T9") (pinfunction "TDI_0_T9") (pintype "input"))
      (node (ref "J6") (pin "10") (pinfunction "10_10") (pintype "bidirectional"))
    )
    (net (code "5") (name "/CFG_TDO") (class "Default")
      (node (ref "D3") (pin "2") (pinfunction "I/O1_2") (pintype "bidirectional"))
      (node (ref "IC4") (pin "T8") (pinfunction "TDO_0_T8") (pintype "output"))
      (node (ref "J6") (pin "8") (pinfunction "8_8") (pintype "bidirectional"))
    )
    (net (code "6") (name "/CFG_TMS") (class "Default")
      (node (ref "D2") (pin "2") (pinfunction "I/O1_2") (pintype "bidirectional"))
      (node (ref "IC4") (pin "R8") (pinfunction "TMS_0_R8") (pintype "input"))
      (node (ref "J6") (pin "4") (pinfunction "4_4") (pintype "bidirectional"))
    )
    (net (code "7") (name "/EN_USB_JTAG") (class "Default")
      (node (ref "C134") (pin "2") (pinfunction "2_2") (pintype "passive"))
      (node (ref "J6") (pin "13") (pinfunction "13_13") (pintype "bidirectional"))
      (node (ref "R49") (pin "1") (pinfunction "1_1") (pintype "passive"))
    )
    (net (code "8") (name "/FLASH_UP_EN") (class "Default")
      (node (ref "IC17") (pin "12") (pinfunction "E_12") (pintype "input"))
      (node (ref "IC17") (pin "13") (pinfunction "E_13") (pintype "input"))
      (node (ref "IC17") (pin "5") (pinfunction "E_5") (pintype "input"))
      (node (ref "IC17") (pin "6") (pinfunction "E_6") (pintype "input"))
      (node (ref "P1") (pin "4") (pinfunction "4_4") (pintype "passive"))
      (node (ref "R54") (pin "2") (pinfunction "2_2") (pintype "passive"))
    )
    (net (code "9") (name "/FLASH_VCC") (class "Default")
      (node (ref "C133") (pin "2") (pinfunction "2_2") (pintype "passive"))
      (node (ref "C332") (pin "1") (pinfunction "1_1") (pintype "passive"))
      (node (ref "FB1") (pin "2") (pinfunction "2_2") (pintype "passive"))
      (node (ref "IC17") (pin "14") (pinfunction "VCC_14") (pintype "power_in"))
      (node (ref "IC6") (pin "8") (pinfunction "VCC_8") (pintype "power_in"))
    )
    (net (code "10") (name "/FPGA_DONE") (class "Default")
      (node (ref "IC4") (pin "F12") (pinfunction "DONE_0_F12") (pintype "bidirectional"))
      (node (ref "P1") (pin "6") (pinfunction "6_6") (pintype "passive"))
      (node (ref "R50") (pin "1") (pinfunction "1_1") (pintype "passive"))
      (node (ref "T6") (pin "1") (pinfunction "G_1") (pintype "passive"))
    )
    (net (code "11") (name "/FPGA_INIT_B") (class "Default")
      (node (ref "IC4") (pin "T10") (pinfunction "INIT_B_0_T10") (pintype "bidirectional"))
      (node (ref "P1") (pin "2") (pinfunction "2_2") (pintype "passive"))
      (node (ref "R44") (pin "1") (pinfunction "1_1") (pintype "passive"))
    )
    (net (code "12") (name "/QSPI_CS") (class "Default")
      (node (ref "IC17") (pin "10") (pinfunction "Z_10") (pintype "bidirectional"))
      (node (ref "IC6") (pin "1") (pinfunction "~{CS}_1") (pintype "input"))
      (node (ref "R45") (pin "2") (pinfunction "2_2") (pintype "passive"))
    )
    (net (code "13") (name "/QSPI_DQ0") (class "Default")
      (node (ref "IC17") (pin "3") (pinfunction "Z_3") (pintype "bidirectional"))
      (node (ref "IC6") (pin "5") (pinfunction "SI/SIO0_5") (pintype "bidirectional"))
    )
    (net (code "14") (name "/QSPI_DQ1") (class "Default")
      (node (ref "IC17") (pin "9") (pinfunction "Z_9") (pintype "bidirectional"))
      (node (ref "IC6") (pin "2") (pinfunction "SO/SIO1_2") (pintype "bidirectional"))
    )
    (net (code "15") (name "/QSPI_DQ2") (class "Default")
      (node (ref "IC6") (pin "3") (pinfunction "~{WP}/SIO2_3") (pintype "bidirectional"))
      (node (ref "R46") (pin "2") (pinfunction "2_2") (pintype "passive"))
    )
    (net (code "16") (name "/QSPI_DQ3") (class "Default")
      (node (ref "IC6") (pin "7") (pinfunction "~{RESET}/SIO3_7") (pintype "bidirectional"))
      (node (ref "R47") (pin "2") (pinfunction "2_2") (pintype "passive"))
    )
    (net (code "17") (name "/SC_MISO") (class "Default")
      (node (ref "IC17") (pin "8") (pinfunction "Y_8") (pintype "bidirectional"))
      (node (ref "P1") (pin "5") (pinfunction "5_5") (pintype "passive"))
    )
    (net (code "18") (name "/SC_MOSI") (class "Default")
      (node (ref "IC17") (pin "4") (pinfunction "Y_4") (pintype "bidirectional"))
      (node (ref "P1") (pin "3") (pinfunction "3_3") (pintype "passive"))
    )
    (net (code "19") (name "/SC_SCLK") (class "Default")
      (node (ref "IC17") (pin "1") (pinfunction "Y_1") (pintype "bidirectional"))
      (node (ref "P1") (pin "1") (pinfunction "1_1") (pintype "passive"))
    )
    (net (code "20") (name "/SC_SSEL") (class "Default")
      (node (ref "IC17") (pin "11") (pinfunction "Y_11") (pintype "bidirectional"))
      (node (ref "P1") (pin "7") (pinfunction "7_7") (pintype "passive"))
    )
    (net (code "22") (name "GND") (class "Default")
      (node (ref "C100") (pin "1") (pinfunction "1_1") (pintype "passive"))
      (node (ref "C101") (pin "1") (pinfunction "1_1") (pintype "passive"))
      (node (ref "C102") (pin "1") (pinfunction "1_1") (pintype "passive"))
      (node (ref "C103") (pin "2") (pinfunction "2_2") (pintype "passive"))
      (node (ref "C104") (pin "2") (pinfunction "2_2") (pintype "passive"))
      (node (ref "C105") (pin "1") (pinfunction "1_1") (pintype "passive"))
      (node (ref "C106") (pin "1") (pinfunction "1_1") (pintype "passive"))
      (node (ref "C107") (pin "1") (pinfunction "1_1") (pintype "passive"))
      (node (ref "C108") (pin "1") (pinfunction "1_1") (pintype "passive"))
      (node (ref "C109") (pin "1") (pinfunction "1_1") (pintype "passive"))
      (node (ref "C110") (pin "1") (pinfunction "1_1") (pintype "passive"))
      (node (ref "C111") (pin "1") (pinfunction "1_1") (pintype "passive"))
      (node (ref "C112") (pin "1") (pinfunction "1_1") (pintype "passive"))
      (node (ref "C113") (pin "1") (pinfunction "1_1") (pintype "passive"))
      (node (ref "C114") (pin "1") (pinfunction "1_1") (pintype "passive"))
      (node (ref "C115") (pin "1") (pinfunction "1_1") (pintype "passive"))
      (node (ref "C116") (pin "1") (pinfunction "1_1") (pintype "passive"))
      (node (ref "C117") (pin "1") (pinfunction "1_1") (pintype "passive"))
      (node (ref "C118") (pin "1") (pinfunction "1_1") (pintype "passive"))
      (node (ref "C119") (pin "1") (pinfunction "1_1") (pintype "passive"))
      (node (ref "C120") (pin "1") (pinfunction "1_1") (pintype "passive"))
      (node (ref "C121") (pin "1") (pinfunction "1_1") (pintype "passive"))
      (node (ref "C122") (pin "1") (pinfunction "1_1") (pintype "passive"))
      (node (ref "C123") (pin "1") (pinfunction "1_1") (pintype "passive"))
      (node (ref "C124") (pin "1") (pinfunction "1_1") (pintype "passive"))
      (node (ref "C125") (pin "1") (pinfunction "1_1") (pintype "passive"))
      (node (ref "C126") (pin "1") (pinfunction "1_1") (pintype "passive"))
      (node (ref "C127") (pin "1") (pinfunction "1_1") (pintype "passive"))
      (node (ref "C128") (pin "1") (pinfunction "1_1") (pintype "passive"))
      (node (ref "C129") (pin "1") (pinfunction "1_1") (pintype "passive"))
      (node (ref "C130") (pin "1") (pinfunction "1_1") (pintype "passive"))
      (node (ref "C131") (pin "1") (pinfunction "1_1") (pintype "passive"))
      (node (ref "C132") (pin "1") (pinfunction "1_1") (pintype "passive"))
      (node (ref "C133") (pin "1") (pinfunction "1_1") (pintype "passive"))
      (node (ref "C134") (pin "1") (pinfunction "1_1") (pintype "passive"))
      (node (ref "C332") (pin "2") (pinfunction "2_2") (pintype "passive"))
      (node (ref "C56") (pin "1") (pinfunction "1_1") (pintype "passive"))
      (node (ref "C57") (pin "1") (pinfunction "1_1") (pintype "passive"))
      (node (ref "C58") (pin "1") (pinfunction "1_1") (pintype "passive"))
      (node (ref "C59") (pin "1") (pinfunction "1_1") (pintype "passive"))
      (node (ref "C60") (pin "1") (pinfunction "1_1") (pintype "passive"))
      (node (ref "C61") (pin "1") (pinfunction "1_1") (pintype "passive"))
      (node (ref "C62") (pin "1") (pinfunction "1_1") (pintype "passive"))
      (node (ref "C63") (pin "1") (pinfunction "1_1") (pintype "passive"))
      (node (ref "C64") (pin "1") (pinfunction "1_1") (pintype "passive"))
      (node (ref "C65") (pin "1") (pinfunction "1_1") (pintype "passive"))
      (node (ref "C66") (pin "1") (pinfunction "1_1") (pintype "passive"))
      (node (ref "C67") (pin "1") (pinfunction "1_1") (pintype "passive"))
      (node (ref "C68") (pin "1") (pinfunction "1_1") (pintype "passive"))
      (node (ref "C69") (pin "1") (pinfunction "1_1") (pintype "passive"))
      (node (ref "C70") (pin "1") (pinfunction "1_1") (pintype "passive"))
      (node (ref "C71") (pin "1") (pinfunction "1_1") (pintype "passive"))
      (node (ref "C72") (pin "1") (pinfunction "1_1") (pintype "passive"))
      (node (ref "C73") (pin "1") (pinfunction "1_1") (pintype "passive"))
      (node (ref "C74") (pin "1") (pinfunction "1_1") (pintype "passive"))
      (node (ref "C75") (pin "1") (pinfunction "1_1") (pintype "passive"))
      (node (ref "C76") (pin "1") (pinfunction "1_1") (pintype "passive"))
      (node (ref "C77") (pin "1") (pinfunction "1_1") (pintype "passive"))
      (node (ref "C78") (pin "1") (pinfunction "1_1") (pintype "passive"))
      (node (ref "C79") (pin "1") (pinfunction "1_1") (pintype "passive"))
      (node (ref "C80") (pin "1") (pinfunction "1_1") (pintype "passive"))
      (node (ref "C81") (pin "1") (pinfunction "1_1") (pintype "passive"))
      (node (ref "C82") (pin "1") (pinfunction "1_1") (pintype "passive"))
      (node (ref "C83") (pin "1") (pinfunction "1_1") (pintype "passive"))
      (node (ref "C84") (pin "1") (pinfunction "1_1") (pintype "passive"))
      (node (ref "C85") (pin "1") (pinfunction "1_1") (pintype "passive"))
      (node (ref "C86") (pin "1") (pinfunction "1_1") (pintype "passive"))
      (node (ref "C87") (pin "1") (pinfunction "1_1") (pintype "passive"))
      (node (ref "C88") (pin "1") (pinfunction "1_1") (pintype "passive"))
      (node (ref "C89") (pin "1") (pinfunction "1_1") (pintype "passive"))
      (node (ref "C90") (pin "1") (pinfunction "1_1") (pintype "passive"))
      (node (ref "C91") (pin "1") (pinfunction "1_1") (pintype "passive"))
      (node (ref "C92") (pin "1") (pinfunction "1_1") (pintype "passive"))
      (node (ref "C93") (pin "1") (pinfunction "1_1") (pintype "passive"))
      (node (ref "C94") (pin "1") (pinfunction "1_1") (pintype "passive"))
      (node (ref "C95") (pin "1") (pinfunction "1_1") (pintype "passive"))
      (node (ref "C96") (pin "1") (pinfunction "1_1") (pintype "passive"))
      (node (ref "C97") (pin "1") (pinfunction "1_1") (pintype "passive"))
      (node (ref "C98") (pin "1") (pinfunction "1_1") (pintype "passive"))
      (node (ref "C99") (pin "1") (pinfunction "1_1") (pintype "passive"))
      (node (ref "D2") (pin "1") (pinfunction "GND_1") (pintype "power_in"))
      (node (ref "D3") (pin "1") (pinfunction "GND_1") (pintype "power_in"))
      (node (ref "IC17") (pin "7") (pinfunction "GND_7") (pintype "power_in"))
      (node (ref "IC4") (pin "A1") (pinfunction "GND_A1") (pintype "power_in"))
      (node (ref "IC4") (pin "A11") (pinfunction "GND_A11") (pintype "power_in"))
      (node (ref "IC4") (pin "A18") (pinfunction "GND_A18") (pintype "power_in"))
      (node (ref "IC4") (pin "A5") (pinfunction "GND_A5") (pintype "power_in"))
      (node (ref "IC4") (pin "A7") (pinfunction "GND_A7") (pintype "power_in"))
      (node (ref "IC4") (pin "A8") (pinfunction "GND_A8") (pintype "power_in"))
      (node (ref "IC4") (pin "B18") (pinfunction "GND_B18") (pintype "power_in"))
      (node (ref "IC4") (pin "B3") (pinfunction "GND_B3") (pintype "power_in"))
      (node (ref "IC4") (pin "B7") (pinfunction "GND_B7") (pintype "power_in"))
      (node (ref "IC4") (pin "B8") (pinfunction "GND_B8") (pintype "power_in"))
      (node (ref "IC4") (pin "C15") (pinfunction "GND_C15") (pintype "power_in"))
      (node (ref "IC4") (pin "C2") (pinfunction "GND_C2") (pintype "power_in"))
      (node (ref "IC4") (pin "C6") (pinfunction "GND_C6") (pintype "power_in"))
      (node (ref "IC4") (pin "C7") (pinfunction "GND_C7") (pintype "power_in"))
      (node (ref "IC4") (pin "D12") (pinfunction "GND_D12") (pintype "power_in"))
      (node (ref "IC4") (pin "D3") (pinfunction "GND_D3") (pintype "power_in"))
      (node (ref "IC4") (pin "D4") (pinfunction "GND_D4") (pintype "power_in"))
      (node (ref "IC4") (pin "D7") (pinfunction "GND_D7") (pintype "power_in"))
      (node (ref "IC4") (pin "E2") (pinfunction "GND_E2") (pintype "power_in"))
      (node (ref "IC4") (pin "E6") (pinfunction "GND_E6") (pintype "power_in"))
      (node (ref "IC4") (pin "E7") (pinfunction "GND_E7") (pintype "power_in"))
      (node (ref "IC4") (pin "E9") (pinfunction "GND_E9") (pintype "power_in"))
      (node (ref "IC4") (pin "F10") (pinfunction "GND_F10") (pintype "power_in"))
      (node (ref "IC4") (pin "F13") (pinfunction "M2_0_F13") (pintype "input"))
      (node (ref "IC4") (pin "F16") (pinfunction "GND_F16") (pintype "power_in"))
      (node (ref "IC4") (pin "F4") (pinfunction "GND_F4") (pintype "power_in"))
      (node (ref "IC4") (pin "F6") (pinfunction "GND_F6") (pintype "power_in"))
      (node (ref "IC4") (pin "G1") (pinfunction "GND_G1") (pintype "power_in"))
      (node (ref "IC4") (pin "G11") (pinfunction "GND_G11") (pintype "power_in"))
      (node (ref "IC4") (pin "G13") (pinfunction "GND_G13") (pintype "power_in"))
      (node (ref "IC4") (pin "G5") (pinfunction "GND_G5") (pintype "power_in"))
      (node (ref "IC4") (pin "G6") (pinfunction "GND_G6") (pintype "power_in"))
      (node (ref "IC4") (pin "G7") (pinfunction "GND_G7") (pintype "power_in"))
      (node (ref "IC4") (pin "G9") (pinfunction "GND_G9") (pintype "power_in"))
      (node (ref "IC4") (pin "H10") (pinfunction "GND_H10") (pintype "power_in"))
      (node (ref "IC4") (pin "H12") (pinfunction "GND_H12") (pintype "power_in"))
      (node (ref "IC4") (pin "H3") (pinfunction "GND_H3") (pintype "power_in"))
      (node (ref "IC4") (pin "H4") (pinfunction "GND_H4") (pintype "power_in"))
      (node (ref "IC4") (pin "H5") (pinfunction "GND_H5") (pintype "power_in"))
      (node (ref "IC4") (pin "H6") (pinfunction "GND_H6") (pintype "power_in"))
      (node (ref "IC4") (pin "H8") (pinfunction "GND_H8") (pintype "power_in"))
      (node (ref "IC4") (pin "J1") (pinfunction "GND_J1") (pintype "power_in"))
      (node (ref "IC4") (pin "J11") (pinfunction "GND_J11") (pintype "power_in"))
      (node (ref "IC4") (pin "J13") (pinfunction "GND_J13") (pintype "power_in"))
      (node (ref "IC4") (pin "J17") (pinfunction "GND_J17") (pintype "power_in"))
      (node (ref "IC4") (pin "J2") (pinfunction "GND_J2") (pintype "power_in"))
      (node (ref "IC4") (pin "J3") (pinfunction "GND_J3") (pintype "power_in"))
      (node (ref "IC4") (pin "J7") (pinfunction "GND_J7") (pintype "power_in"))
      (node (ref "IC4") (pin "K12") (pinfunction "GND_K12") (pintype "power_in"))
      (node (ref "IC4") (pin "K14") (pinfunction "GND_K14") (pintype "power_in"))
      (node (ref "IC4") (pin "K4") (pinfunction "GND_K4") (pintype "power_in"))
      (node (ref "IC4") (pin "K8") (pinfunction "GND_K8") (pintype "power_in"))
      (node (ref "IC4") (pin "K9") (pinfunction "VREFN_0_K9") (pintype "input"))
      (node (ref "IC4") (pin "L1") (pinfunction "GND_L1") (pintype "power_in"))
      (node (ref "IC4") (pin "L10") (pinfunction "VREFP_0_L10") (pintype "input"))
      (node (ref "IC4") (pin "L11") (pinfunction "GND_L11") (pintype "power_in"))
      (node (ref "IC4") (pin "L13") (pinfunction "GND_L13") (pintype "power_in"))
      (node (ref "IC4") (pin "L7") (pinfunction "GND_L7") (pintype "power_in"))
      (node (ref "IC4") (pin "L9") (pinfunction "VN_0_L9") (pintype "input"))
      (node (ref "IC4") (pin "M10") (pinfunction "DXP_0_M10") (pintype "input"))
      (node (ref "IC4") (pin "M12") (pinfunction "GND_M12") (pintype "power_in"))
      (node (ref "IC4") (pin "M18") (pinfunction "GND_M18") (pintype "power_in"))
      (node (ref "IC4") (pin "M8") (pinfunction "GND_M8") (pintype "power_in"))
      (node (ref "IC4") (pin "M9") (pinfunction "DXN_0_M9") (pintype "input"))
      (node (ref "IC4") (pin "N11") (pinfunction "GND_N11") (pintype "power_in"))
      (node (ref "IC4") (pin "N13") (pinfunction "GND_N13") (pintype "power_in"))
      (node (ref "IC4") (pin "N15") (pinfunction "GND_N15") (pintype "power_in"))
      (node (ref "IC4") (pin "N5") (pinfunction "GND_N5") (pintype "power_in"))
      (node (ref "IC4") (pin "N7") (pinfunction "GND_N7") (pintype "power_in"))
      (node (ref "IC4") (pin "N9") (pinfunction "GND_N9") (pintype "power_in"))
      (node (ref "IC4") (pin "P12") (pinfunction "GND_P12") (pintype "power_in"))
      (node (ref "IC4") (pin "P2") (pinfunction "GND_P2") (pintype "power_in"))
      (node (ref "IC4") (pin "P8") (pinfunction "GND_P8") (pintype "power_in"))
      (node (ref "IC4") (pin "R11") (pinfunction "M1_0_R11") (pintype "input"))
      (node (ref "IC4") (pin "R9") (pinfunction "GND_R9") (pintype "power_in"))
      (node (ref "IC4") (pin "T16") (pinfunction "GND_T16") (pintype "power_in"))
      (node (ref "IC4") (pin "T6") (pinfunction "GND_T6") (pintype "power_in"))
      (node (ref "IC4") (pin "U13") (pinfunction "GND_U13") (pintype "power_in"))
      (node (ref "IC4") (pin "U3") (pinfunction "GND_U3") (pintype "power_in"))
      (node (ref "IC4") (pin "V1") (pinfunction "GND_V1") (pintype "power_in"))
      (node (ref "IC4") (pin "V10") (pinfunction "GND_V10") (pintype "power_in"))
      (node (ref "IC4") (pin "V18") (pinfunction "GND_V18") (pintype "power_in"))
      (node (ref "IC5") (pin "3") (pinfunction "VSS_3") (pintype "power_in"))
      (node (ref "IC6") (pin "4") (pinfunction "GND_4") (pintype "power_in"))
      (node (ref "IC6") (pin "9") (pinfunction "EP_9") (pintype "power_in"))
      (node (ref "J6") (pin "1") (pinfunction "1_1") (pintype "bidirectional"))
      (node (ref "J6") (pin "11") (pinfunction "11_11") (pintype "bidirectional"))
      (node (ref "J6") (pin "3") (pinfunction "3_3") (pintype "bidirectional"))
      (node (ref "J6") (pin "5") (pinfunction "5_5") (pintype "bidirectional"))
      (node (ref "J6") (pin "7") (pinfunction "7_7") (pintype "bidirectional"))
      (node (ref "J6") (pin "9") (pinfunction "9_9") (pintype "bidirectional"))
      (node (ref "L1") (pin "2") (pinfunction "2_2") (pintype "passive"))
      (node (ref "P1") (pin "8") (pinfunction "8_8") (pintype "passive"))
      (node (ref "R147") (pin "2") (pinfunction "2_2") (pintype "passive"))
      (node (ref "R54") (pin "1") (pinfunction "1_1") (pintype "passive"))
      (node (ref "T6") (pin "2") (pinfunction "S_2") (pintype "passive"))
    )
    (net (code "23") (name "MGTAVCC") (class "Default")
      (node (ref "C56") (pin "2") (pinfunction "2_2") (pintype "passive"))
      (node (ref "C57") (pin "2") (pinfunction "2_2") (pintype "passive"))
      (node (ref "C58") (pin "2") (pinfunction "2_2") (pintype "passive"))
      (node (ref "C59") (pin "2") (pinfunction "2_2") (pintype "passive"))
      (node (ref "C60") (pin "2") (pinfunction "2_2") (pintype "passive"))
      (node (ref "C61") (pin "2") (pinfunction "2_2") (pintype "passive"))
      (node (ref "IC4") (pin "B4") (pinfunction "MGTAVCC_B4") (pintype "power_in"))
      (node (ref "IC4") (pin "C5") (pinfunction "MGTAVCC_C5") (pintype "power_in"))
      (node (ref "IC4") (pin "E5") (pinfunction "MGTAVCC_E5") (pintype "power_in"))
      (node (ref "IC4") (pin "F5") (pinfunction "MGTAVCC_F5") (pintype "power_in"))
    )
    (net (code "24") (name "MGTAVTT") (class "Default")
      (node (ref "C62") (pin "2") (pinfunction "2_2") (pintype "passive"))
      (node (ref "C63") (pin "2") (pinfunction "2_2") (pintype "passive"))
      (node (ref "C64") (pin "2") (pinfunction "2_2") (pintype "passive"))
      (node (ref "C65") (pin "2") (pinfunction "2_2") (pintype "passive"))
      (node (ref "C66") (pin "2") (pinfunction "2_2") (pintype "passive"))
      (node (ref "C67") (pin "2") (pinfunction "2_2") (pintype "passive"))
      (node (ref "IC4") (pin "A2") (pinfunction "MGTAVTT_A2") (pintype "power_in"))
      (node (ref "IC4") (pin "C1") (pinfunction "MGTAVTT_C1") (pintype "power_in"))
      (node (ref "IC4") (pin "E1") (pinfunction "MGTAVTT_E1") (pintype "power_in"))
      (node (ref "IC4") (pin "F3") (pinfunction "MGTAVTT_F3") (pintype "power_in"))
      (node (ref "IC4") (pin "G2") (pinfunction "MGTAVTT_G2") (pintype "power_in"))
    )
    (net (code "25") (name "Net-(IC4D-PROGRAM_B_0)") (class "Default")
      (node (ref "IC4") (pin "P10") (pinfunction "PROGRAM_B_0_P10") (pintype "input"))
      (node (ref "R43") (pin "1") (pinfunction "1_1") (pintype "passive"))
    )
    (net (code "26") (name "Net-(IC4D-VP_0)") (class "Default")
      (node (ref "IC4") (pin "K10") (pinfunction "VP_0_K10") (pintype "input"))
      (node (ref "R147") (pin "1") (pinfunction "1_1") (pintype "passive"))
    )
    (net (code "27") (name "Net-(IC4I-GNDADC_0)") (class "Default")
      (node (ref "IC4") (pin "J9") (pinfunction "GNDADC_0_J9") (pintype "power_in"))
      (node (ref "L1") (pin "1") (pinfunction "1_1") (pintype "passive"))
    )
    (net (code "28") (name "Net-(IC5-~{RST})") (class "Default")
      (node (ref "IC5") (pin "1") (pinfunction "~{RST}_1") (pintype "open_collector"))
      (node (ref "R170") (pin "1") (pinfunction "1_1") (pintype "passive"))
      (node (ref "R44") (pin "2") (pinfunction "2_2") (pintype "passive"))
    )
    (net (code "29") (name "Net-(LD8-A)") (class "Default")
      (node (ref "LD8") (pin "2") (pinfunction "A_2") (pintype "passive"))
      (node (ref "R48") (pin "1") (pinfunction "1_1") (pintype "passive"))
    )
    (net (code "30") (name "Net-(LD8-C)") (class "Default")
      (node (ref "LD8") (pin "1") (pinfunction "C_1") (pintype "passive"))
      (node (ref "T6") (pin "3") (pinfunction "D_3") (pintype "passive"))
    )
    (net (code "31") (name "P1V0") (class "Default")
      (node (ref "C103") (pin "1") (pinfunction "1_1") (pintype "passive"))
      (node (ref "C104") (pin "1") (pinfunction "1_1") (pintype "passive"))
      (node (ref "C107") (pin "2") (pinfunction "2_2") (pintype "passive"))
      (node (ref "C108") (pin "2") (pinfunction "2_2") (pintype "passive"))
      (node (ref "C109") (pin "2") (pinfunction "2_2") (pintype "passive"))
      (node (ref "C110") (pin "2") (pinfunction "2_2") (pintype "passive"))
      (node (ref "C111") (pin "2") (pinfunction "2_2") (pintype "passive"))
      (node (ref "C112") (pin "2") (pinfunction "2_2") (pintype "passive"))
      (node (ref "C120") (pin "2") (pinfunction "2_2") (pintype "passive"))
      (node (ref "C121") (pin "2") (pinfunction "2_2") (pintype "passive"))
      (node (ref "C122") (pin "2") (pinfunction "2_2") (pintype "passive"))
      (node (ref "C123") (pin "2") (pinfunction "2_2") (pintype "passive"))
      (node (ref "C124") (pin "2") (pinfunction "2_2") (pintype "passive"))
      (node (ref "C125") (pin "2") (pinfunction "2_2") (pintype "passive"))
      (node (ref "C126") (pin "2") (pinfunction "2_2") (pintype "passive"))
      (node (ref "C127") (pin "2") (pinfunction "2_2") (pintype "passive"))
      (node (ref "C128") (pin "2") (pinfunction "2_2") (pintype "passive"))
      (node (ref "C129") (pin "2") (pinfunction "2_2") (pintype "passive"))
      (node (ref "C130") (pin "2") (pinfunction "2_2") (pintype "passive"))
      (node (ref "C131") (pin "2") (pinfunction "2_2") (pintype "passive"))
      (node (ref "IC4") (pin "F11") (pinfunction "VCCBRAM_F11") (pintype "power_in"))
      (node (ref "IC4") (pin "F7") (pinfunction "VCCINT_F7") (pintype "power_in"))
      (node (ref "IC4") (pin "F9") (pinfunction "VCCINT_F9") (pintype "power_in"))
      (node (ref "IC4") (pin "G10") (pinfunction "VCCBRAM_G10") (pintype "power_in"))
      (node (ref "IC4") (pin "G8") (pinfunction "VCCINT_G8") (pintype "power_in"))
      (node (ref "IC4") (pin "H11") (pinfunction "VCCBRAM_H11") (pintype "power_in"))
      (node (ref "IC4") (pin "H7") (pinfunction "VCCINT_H7") (pintype "power_in"))
      (node (ref "IC4") (pin "H9") (pinfunction "VCCINT_H9") (pintype "power_in"))
      (node (ref "IC4") (pin "J12") (pinfunction "VCCINT_J12") (pintype "power_in"))
      (node (ref "IC4") (pin "J8") (pinfunction "VCCINT_J8") (pintype "power_in"))
      (node (ref "IC4") (pin "K11") (pinfunction "VCCINT_K11") (pintype "power_in"))
      (node (ref "IC4") (pin "K7") (pinfunction "VCCINT_K7") (pintype "power_in"))
      (node (ref "IC4") (pin "L12") (pinfunction "VCCINT_L12") (pintype "power_in"))
      (node (ref "IC4") (pin "L8") (pinfunction "VCCINT_L8") (pintype "power_in"))
      (node (ref "IC4") (pin "M11") (pinfunction "VCCINT_M11") (pintype "power_in"))
      (node (ref "IC4") (pin "M7") (pinfunction "VCCINT_M7") (pintype "power_in"))
      (node (ref "IC4") (pin "N10") (pinfunction "VCCINT_N10") (pintype "power_in"))
      (node (ref "IC4") (pin "N12") (pinfunction "VCCINT_N12") (pintype "power_in"))
      (node (ref "IC4") (pin "N8") (pinfunction "VCCINT_N8") (pintype "power_in"))
      (node (ref "IC4") (pin "P11") (pinfunction "VCCINT_P11") (pintype "power_in"))
      (node (ref "IC4") (pin "P9") (pinfunction "VCCINT_P9") (pintype "power_in"))
    )
    (net (code "32") (name "P1V8") (class "Default")
      (node (ref "C113") (pin "2") (pinfunction "2_2") (pintype "passive"))
      (node (ref "C114") (pin "2") (pinfunction "2_2") (pintype "passive"))
      (node (ref "C115") (pin "2") (pinfunction "2_2") (pintype "passive"))
      (node (ref "C116") (pin "2") (pinfunction "2_2") (pintype "passive"))
      (node (ref "C117") (pin "2") (pinfunction "2_2") (pintype "passive"))
      (node (ref "C118") (pin "2") (pinfunction "2_2") (pintype "passive"))
      (node (ref "C119") (pin "2") (pinfunction "2_2") (pintype "passive"))
      (node (ref "IC4") (pin "E11") (pinfunction "VCCBATT_0_E11") (pintype "power_in"))
      (node (ref "IC4") (pin "G12") (pinfunction "VCCAUX_G12") (pintype "power_in"))
      (node (ref "IC4") (pin "H13") (pinfunction "VCCAUX_H13") (pintype "power_in"))
      (node (ref "IC4") (pin "K13") (pinfunction "VCCAUX_K13") (pintype "power_in"))
      (node (ref "IC4") (pin "M13") (pinfunction "VCCAUX_M13") (pintype "power_in"))
      (node (ref "IC4") (pin "P13") (pinfunction "VCCAUX_P13") (pintype "power_in"))
      (node (ref "L2") (pin "2") (pinfunction "2_2") (pintype "passive"))
    )
    (net (code "33") (name "P2V5") (class "Default")
      (node (ref "C71") (pin "2") (pinfunction "2_2") (pintype "passive"))
      (node (ref "C72") (pin "2") (pinfunction "2_2") (pintype "passive"))
      (node (ref "C73") (pin "2") (pinfunction "2_2") (pintype "passive"))
      (node (ref "C74") (pin "2") (pinfunction "2_2") (pintype "passive"))
      (node (ref "C75") (pin "2") (pinfunction "2_2") (pintype "passive"))
      (node (ref "C76") (pin "2") (pinfunction "2_2") (pintype "passive"))
      (node (ref "C77") (pin "2") (pinfunction "2_2") (pintype "passive"))
      (node (ref "C78") (pin "2") (pinfunction "2_2") (pintype "passive"))
      (node (ref "C79") (pin "2") (pinfunction "2_2") (pintype "passive"))
      (node (ref "C80") (pin "2") (pinfunction "2_2") (pintype "passive"))
      (node (ref "C81") (pin "2") (pinfunction "2_2") (pintype "passive"))
      (node (ref "C82") (pin "2") (pinfunction "2_2") (pintype "passive"))
      (node (ref "C83") (pin "2") (pinfunction "2_2") (pintype "passive"))
      (node (ref "IC4") (pin "A16") (pinfunction "VCCO_15_A16") (pintype "power_in"))
      (node (ref "IC4") (pin "B13") (pinfunction "VCCO_15_B13") (pintype "power_in"))
      (node (ref "IC4") (pin "C10") (pinfunction "VCCO_15_C10") (pintype "power_in"))
      (node (ref "IC4") (pin "D17") (pinfunction "VCCO_15_D17") (pintype "power_in"))
      (node (ref "IC4") (pin "E14") (pinfunction "VCCO_15_E14") (pintype "power_in"))
      (node (ref "IC4") (pin "G18") (pinfunction "VCCO_15_G18") (pintype "power_in"))
      (node (ref "IC4") (pin "H15") (pinfunction "VCCO_15_H15") (pintype "power_in"))
    )
    (net (code "34") (name "P3V3") (class "Default")
      (node (ref "C100") (pin "2") (pinfunction "2_2") (pintype "passive"))
      (node (ref "C101") (pin "2") (pinfunction "2_2") (pintype "passive"))
      (node (ref "C102") (pin "2") (pinfunction "2_2") (pintype "passive"))
      (node (ref "C132") (pin "2") (pinfunction "2_2") (pintype "passive"))
      (node (ref "C68") (pin "2") (pinfunction "2_2") (pintype "passive"))
      (node (ref "C69") (pin "2") (pinfunction "2_2") (pintype "passive"))
      (node (ref "C70") (pin "2") (pinfunction "2_2") (pintype "passive"))
      (node (ref "C84") (pin "2") (pinfunction "2_2") (pintype "passive"))
      (node (ref "C85") (pin "2") (pinfunction "2_2") (pintype "passive"))
      (node (ref "C86") (pin "2") (pinfunction "2_2") (pintype "passive"))
      (node (ref "C87") (pin "2") (pinfunction "2_2") (pintype "passive"))
      (node (ref "C88") (pin "2") (pinfunction "2_2") (pintype "passive"))
      (node (ref "C89") (pin "2") (pinfunction "2_2") (pintype "passive"))
      (node (ref "C90") (pin "2") (pinfunction "2_2") (pintype "passive"))
      (node (ref "C91") (pin "2") (pinfunction "2_2") (pintype "passive"))
      (node (ref "C92") (pin "2") (pinfunction "2_2") (pintype "passive"))
      (node (ref "C93") (pin "2") (pinfunction "2_2") (pintype "passive"))
      (node (ref "C94") (pin "2") (pinfunction "2_2") (pintype "passive"))
      (node (ref "C95") (pin "2") (pinfunction "2_2") (pintype "passive"))
      (node (ref "C96") (pin "2") (pinfunction "2_2") (pintype "passive"))
      (node (ref "C97") (pin "2") (pinfunction "2_2") (pintype "passive"))
      (node (ref "C98") (pin "2") (pinfunction "2_2") (pintype "passive"))
      (node (ref "C99") (pin "2") (pinfunction "2_2") (pintype "passive"))
      (node (ref "D2") (pin "4") (pinfunction "VCC_4") (pintype "power_in"))
      (node (ref "D3") (pin "4") (pinfunction "VCC_4") (pintype "power_in"))
      (node (ref "FB1") (pin "1") (pinfunction "1_1") (pintype "passive"))
      (node (ref "IC4") (pin "E10") (pinfunction "VCCO_0_E10") (pintype "power_in"))
      (node (ref "IC4") (pin "E12") (pinfunction "CFGBVS_0_E12") (pintype "input"))
      (node (ref "IC4") (pin "L16") (pinfunction "VCCO_14_L16") (pintype "power_in"))
      (node (ref "IC4") (pin "L6") (pinfunction "VCCO_34_L6") (pintype "power_in"))
      (node (ref "IC4") (pin "M3") (pinfunction "VCCO_34_M3") (pintype "power_in"))
      (node (ref "IC4") (pin "P17") (pinfunction "VCCO_14_P17") (pintype "power_in"))
      (node (ref "IC4") (pin "P7") (pinfunction "VCCO_34_P7") (pintype "power_in"))
      (node (ref "IC4") (pin "R10") (pinfunction "VCCO_0_R10") (pintype "power_in"))
      (node (ref "IC4") (pin "R12") (pinfunction "M0_0_R12") (pintype "input"))
      (node (ref "IC4") (pin "R14") (pinfunction "VCCO_14_R14") (pintype "power_in"))
      (node (ref "IC4") (pin "R4") (pinfunction "VCCO_34_R4") (pintype "power_in"))
      (node (ref "IC4") (pin "T1") (pinfunction "VCCO_34_T1") (pintype "power_in"))
      (node (ref "IC4") (pin "T11") (pinfunction "VCCO_14_T11") (pintype "power_in"))
      (node (ref "IC4") (pin "U18") (pinfunction "VCCO_14_U18") (pintype "power_in"))
      (node (ref "IC4") (pin "U8") (pinfunction "VCCO_14_U8") (pintype "power_in"))
      (node (ref "IC4") (pin "V15") (pinfunction "VCCO_14_V15") (pintype "power_in"))
      (node (ref "IC4") (pin "V5") (pinfunction "VCCO_34_V5") (pintype "power_in"))
      (node (ref "IC5") (pin "2") (pinfunction "VDD_2") (pintype "power_in"))
      (node (ref "J6") (pin "2") (pinfunction "2_2") (pintype "bidirectional"))
      (node (ref "R170") (pin "2") (pinfunction "2_2") (pintype "passive"))
      (node (ref "R43") (pin "2") (pinfunction "2_2") (pintype "passive"))
      (node (ref "R45") (pin "1") (pinfunction "1_1") (pintype "passive"))
      (node (ref "R46") (pin "1") (pinfunction "1_1") (pintype "passive"))
      (node (ref "R47") (pin "1") (pinfunction "1_1") (pintype "passive"))
      (node (ref "R48") (pin "2") (pinfunction "2_2") (pintype "passive"))
      (node (ref "R49") (pin "2") (pinfunction "2_2") (pintype "passive"))
      (node (ref "R50") (pin "2") (pinfunction "2_2") (pintype "passive"))
    )
    (net (code "35") (name "VCCADC") (class "Default")
      (node (ref "C105") (pin "2") (pinfunction "2_2") (pintype "passive"))
      (node (ref "C106") (pin "2") (pinfunction "2_2") (pintype "passive"))
      (node (ref "IC4") (pin "J10") (pinfunction "VCCADC_0_J10") (pintype "power_in"))
      (node (ref "L2") (pin "1") (pinfunction "1_1") (pintype "passive"))
    )
    (net (code "36") (name "unconnected-(J6-Pad12)") (class "Default")
      (node (ref "J6") (pin "12") (pinfunction "12_12") (pintype "bidirectional+no_connect"))
    )
    (net (code "37") (name "unconnected-(J6-Pad14)") (class "Default")
      (node (ref "J6") (pin "14") (pinfunction "14_14") (pintype "bidirectional+no_connect"))
    )
  )
)
